# SCH_Satlla_4_Front_side_2023-01-29.net
KiCad netlist of a schematic drawn in EasyEDA
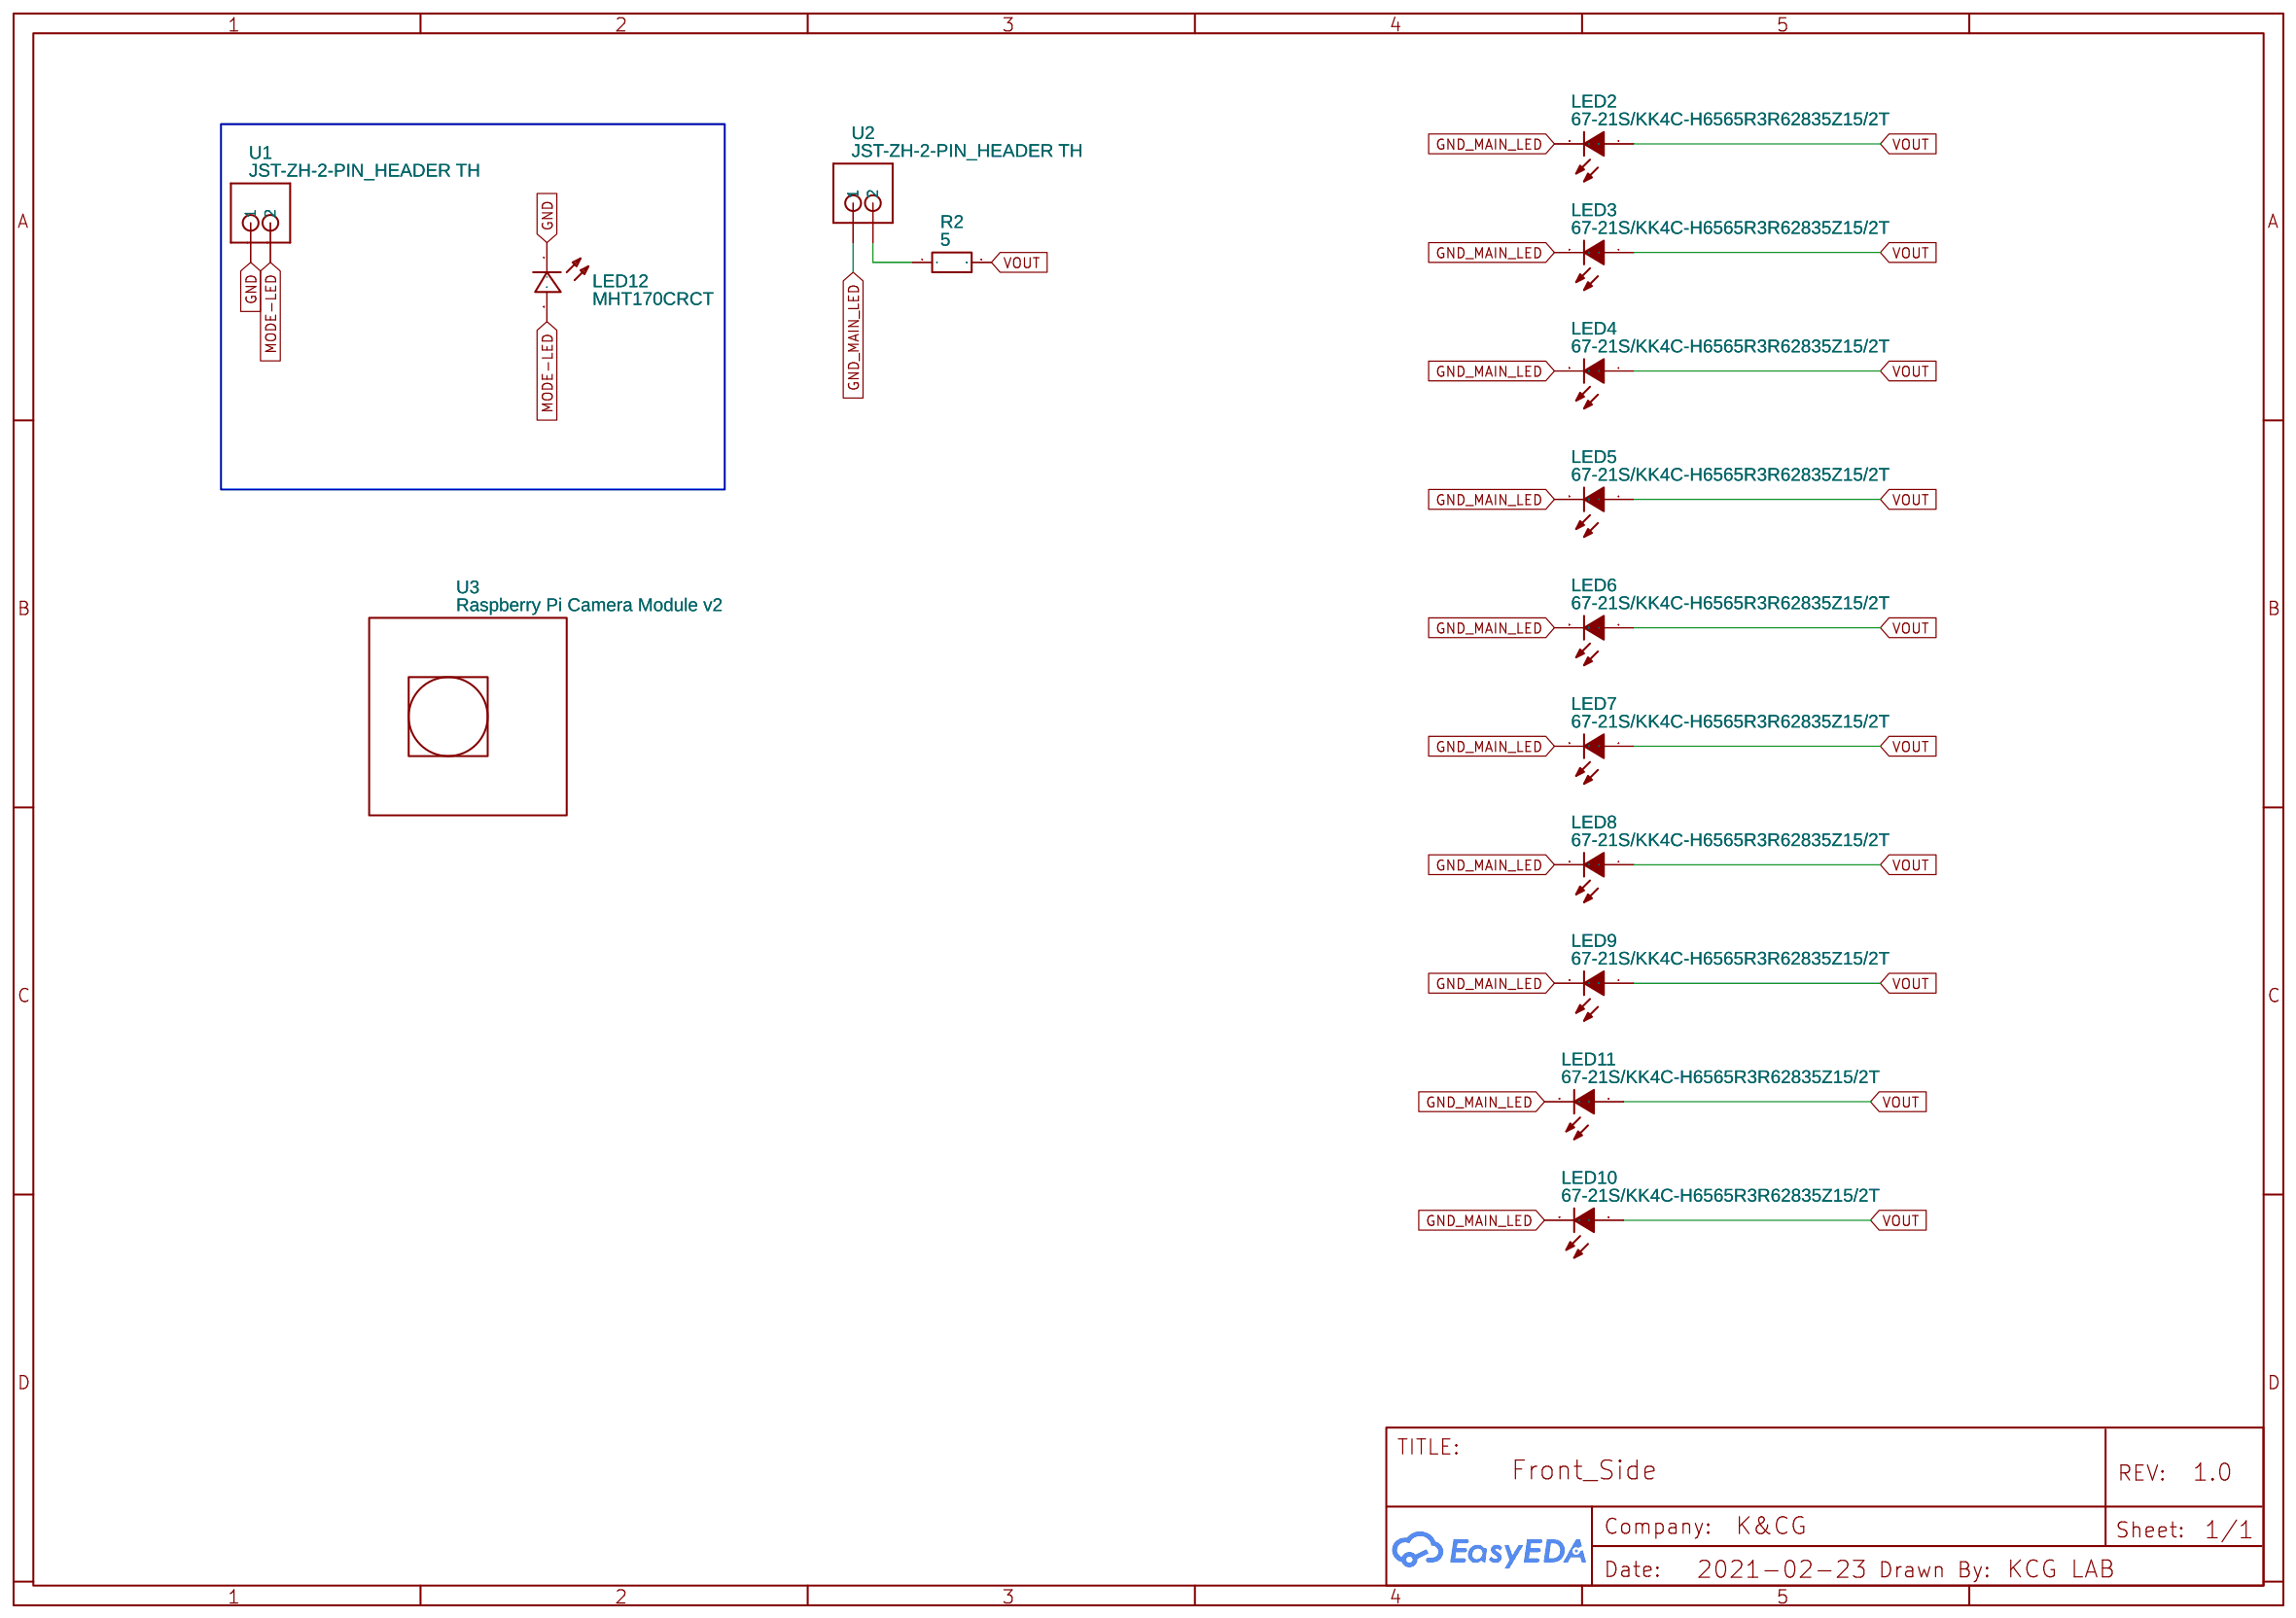
[diagram p0: schematic sheet]

(export (version "E")
  (design (tool "Eeschema 10.0.6"))
  (components
    (comp (ref "LED2")
      (value "67-21S/KK4C-H6565R3R62835Z15/2T")
      (fields (field (name "BOM_Supplier Part") "C73545"))
      (libsource (lib "") (part "67-21S/KK4C-H6565R3R62835Z15/2T"))
    )
    (comp (ref "LED3")
      (value "67-21S/KK4C-H6565R3R62835Z15/2T")
      (fields (field (name "BOM_Supplier Part") "C73545"))
      (libsource (lib "") (part "67-21S/KK4C-H6565R3R62835Z15/2T"))
    )
    (comp (ref "LED4")
      (value "67-21S/KK4C-H6565R3R62835Z15/2T")
      (fields (field (name "BOM_Supplier Part") "C73545"))
      (libsource (lib "") (part "67-21S/KK4C-H6565R3R62835Z15/2T"))
    )
    (comp (ref "LED5")
      (value "67-21S/KK4C-H6565R3R62835Z15/2T")
      (fields (field (name "BOM_Supplier Part") "C73545"))
      (libsource (lib "") (part "67-21S/KK4C-H6565R3R62835Z15/2T"))
    )
    (comp (ref "LED6")
      (value "67-21S/KK4C-H6565R3R62835Z15/2T")
      (fields (field (name "BOM_Supplier Part") "C73545"))
      (libsource (lib "") (part "67-21S/KK4C-H6565R3R62835Z15/2T"))
    )
    (comp (ref "LED7")
      (value "67-21S/KK4C-H6565R3R62835Z15/2T")
      (fields (field (name "BOM_Supplier Part") "C73545"))
      (libsource (lib "") (part "67-21S/KK4C-H6565R3R62835Z15/2T"))
    )
    (comp (ref "LED8")
      (value "67-21S/KK4C-H6565R3R62835Z15/2T")
      (fields (field (name "BOM_Supplier Part") "C73545"))
      (libsource (lib "") (part "67-21S/KK4C-H6565R3R62835Z15/2T"))
    )
    (comp (ref "LED9")
      (value "67-21S/KK4C-H6565R3R62835Z15/2T")
      (fields (field (name "BOM_Supplier Part") "C73545"))
      (libsource (lib "") (part "67-21S/KK4C-H6565R3R62835Z15/2T"))
    )
    (comp (ref "LED10")
      (value "67-21S/KK4C-H6565R3R62835Z15/2T")
      (fields (field (name "BOM_Supplier Part") "C73545"))
      (libsource (lib "") (part "67-21S/KK4C-H6565R3R62835Z15/2T"))
    )
    (comp (ref "LED11")
      (value "67-21S/KK4C-H6565R3R62835Z15/2T")
      (fields (field (name "BOM_Supplier Part") "C73545"))
      (libsource (lib "") (part "67-21S/KK4C-H6565R3R62835Z15/2T"))
    )
    (comp (ref "LED12")
      (value "MHT170CRCT")
      (fields (field (name "BOM_Supplier Part") "C389523"))
      (libsource (lib "") (part "MHT170CRCT"))
    )
    (comp (ref "R2") (value "5") (libsource (lib "") (part "R_1210_EU")))
    (comp (ref "U1") (value "JST-ZH-2-PIN_HEADER TH") (libsource (lib "") (part "JST-ZH-2-PIN_HEADER TH")))
    (comp (ref "U2") (value "JST-ZH-2-PIN_HEADER TH") (libsource (lib "") (part "JST-ZH-2-PIN_HEADER TH")))
    (comp (ref "U3")
      (value "Raspberry Pi Camera Module v2")
      (libsource (lib "") (part "Raspberry Pi Camera Module v2"))
    )
  )
  (nets
    (net (code "1") (name "GND") (class "Default")
      (node (ref "LED12") (pin "1") (pinfunction "-_1") (pintype "unspecified"))
      (node (ref "U1") (pin "1") (pinfunction "1_1") (pintype "unspecified"))
    )
    (net (code "2") (name "GND_MAIN_LED") (class "Default")
      (node (ref "LED10") (pin "2") (pinfunction "C_2") (pintype "input"))
      (node (ref "LED11") (pin "2") (pinfunction "C_2") (pintype "input"))
      (node (ref "LED2") (pin "2") (pinfunction "C_2") (pintype "input"))
      (node (ref "LED3") (pin "2") (pinfunction "C_2") (pintype "input"))
      (node (ref "LED4") (pin "2") (pinfunction "C_2") (pintype "input"))
      (node (ref "LED5") (pin "2") (pinfunction "C_2") (pintype "input"))
      (node (ref "LED6") (pin "2") (pinfunction "C_2") (pintype "input"))
      (node (ref "LED7") (pin "2") (pinfunction "C_2") (pintype "input"))
      (node (ref "LED8") (pin "2") (pinfunction "C_2") (pintype "input"))
      (node (ref "LED9") (pin "2") (pinfunction "C_2") (pintype "input"))
      (node (ref "U2") (pin "1") (pinfunction "1_1") (pintype "unspecified"))
    )
    (net (code "3") (name "MODE-LED") (class "Default")
      (node (ref "LED12") (pin "2") (pinfunction "+_2") (pintype "unspecified"))
      (node (ref "U1") (pin "2") (pinfunction "2_2") (pintype "unspecified"))
    )
    (net (code "4") (name "Net-(R2-Pad1)") (class "Default")
      (node (ref "R2") (pin "1") (pinfunction "1_1") (pintype "unspecified"))
      (node (ref "U2") (pin "2") (pinfunction "2_2") (pintype "unspecified"))
    )
    (net (code "5") (name "VOUT") (class "Default")
      (node (ref "LED10") (pin "1") (pinfunction "A_1") (pintype "input"))
      (node (ref "LED11") (pin "1") (pinfunction "A_1") (pintype "input"))
      (node (ref "LED2") (pin "1") (pinfunction "A_1") (pintype "input"))
      (node (ref "LED3") (pin "1") (pinfunction "A_1") (pintype "input"))
      (node (ref "LED4") (pin "1") (pinfunction "A_1") (pintype "input"))
      (node (ref "LED5") (pin "1") (pinfunction "A_1") (pintype "input"))
      (node (ref "LED6") (pin "1") (pinfunction "A_1") (pintype "input"))
      (node (ref "LED7") (pin "1") (pinfunction "A_1") (pintype "input"))
      (node (ref "LED8") (pin "1") (pinfunction "A_1") (pintype "input"))
      (node (ref "LED9") (pin "1") (pinfunction "A_1") (pintype "input"))
      (node (ref "R2") (pin "2") (pinfunction "2_2") (pintype "unspecified"))
    )
  )
)
